# 01_Main.net
KiCad netlist of a schematic drawn in Altium Designer
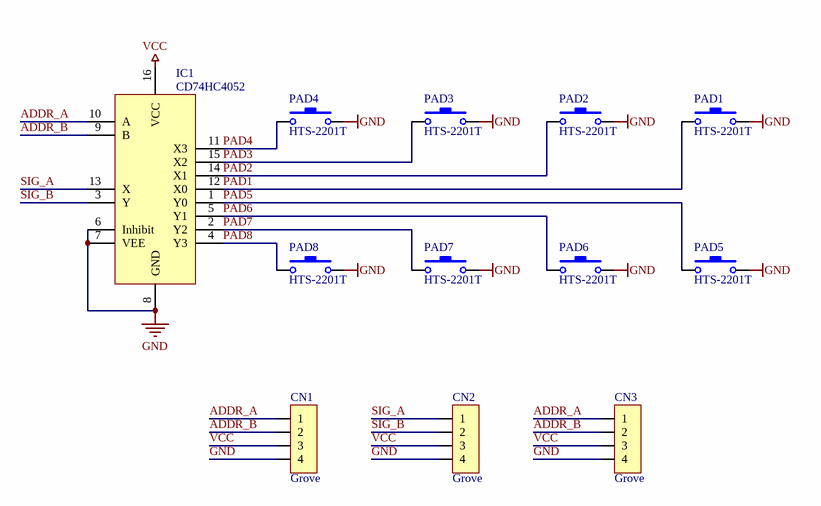
[diagram p0: 01.Main.SchDoc]

(export (version "E")
  (design (tool "Eeschema 10.0.6"))
  (components
    (comp (ref "CN1")
      (value "Grove")
      (footprint "Grove-4P-180D")
      (libsource (lib "MainnoLab library") (part "Connector 1X4"))
    )
    (comp (ref "CN2")
      (value "Grove")
      (footprint "Grove-4P-180D")
      (libsource (lib "MainnoLab library") (part "Connector 1X4"))
    )
    (comp (ref "CN3")
      (value "Grove")
      (footprint "Grove-4P-180D")
      (libsource (lib "MainnoLab library") (part "Connector 1X4"))
    )
    (comp (ref "IC1")
      (value "CD74HC4052")
      (footprint "SOIC16")
      (libsource (lib "MainnoLab library") (part "TC74HC4052AF"))
    )
    (comp (ref "PAD1")
      (value "HTS-2201T")
      (footprint "ALPS-SKHC-12mm")
      (libsource (lib "Jixuan's library") (part "Tact Switch HTS-2201T"))
    )
    (comp (ref "PAD2")
      (value "HTS-2201T")
      (footprint "ALPS-SKHC-12mm")
      (libsource (lib "Jixuan's library") (part "Tact Switch HTS-2201T"))
    )
    (comp (ref "PAD3")
      (value "HTS-2201T")
      (footprint "ALPS-SKHC-12mm")
      (libsource (lib "Jixuan's library") (part "Tact Switch HTS-2201T"))
    )
    (comp (ref "PAD4")
      (value "HTS-2201T")
      (footprint "ALPS-SKHC-12mm")
      (libsource (lib "Jixuan's library") (part "Tact Switch HTS-2201T"))
    )
    (comp (ref "PAD5")
      (value "HTS-2201T")
      (footprint "ALPS-SKHC-12mm")
      (libsource (lib "Jixuan's library") (part "Tact Switch HTS-2201T"))
    )
    (comp (ref "PAD6")
      (value "HTS-2201T")
      (footprint "ALPS-SKHC-12mm")
      (libsource (lib "Jixuan's library") (part "Tact Switch HTS-2201T"))
    )
    (comp (ref "PAD7")
      (value "HTS-2201T")
      (footprint "ALPS-SKHC-12mm")
      (libsource (lib "Jixuan's library") (part "Tact Switch HTS-2201T"))
    )
    (comp (ref "PAD8")
      (value "HTS-2201T")
      (footprint "ALPS-SKHC-12mm")
      (libsource (lib "Jixuan's library") (part "Tact Switch HTS-2201T"))
    )
  )
  (nets
    (net (code "1") (name "/ADDR_A") (class "Default")
      (node (ref "CN1") (pin "1") (pinfunction "1_1") (pintype "passive"))
      (node (ref "CN3") (pin "1") (pinfunction "1_1") (pintype "passive"))
      (node (ref "IC1") (pin "10") (pinfunction "A_10") (pintype "passive"))
    )
    (net (code "2") (name "/ADDR_B") (class "Default")
      (node (ref "CN1") (pin "2") (pinfunction "2_2") (pintype "passive"))
      (node (ref "CN3") (pin "2") (pinfunction "2_2") (pintype "passive"))
      (node (ref "IC1") (pin "9") (pinfunction "B_9") (pintype "passive"))
    )
    (net (code "3") (name "/PAD1") (class "Default")
      (node (ref "IC1") (pin "12") (pinfunction "X0_12") (pintype "passive"))
      (node (ref "PAD1") (pin "2") (pinfunction "2_2") (pintype "passive"))
    )
    (net (code "4") (name "/PAD2") (class "Default")
      (node (ref "IC1") (pin "14") (pinfunction "X1_14") (pintype "passive"))
      (node (ref "PAD2") (pin "2") (pinfunction "2_2") (pintype "passive"))
    )
    (net (code "5") (name "/PAD3") (class "Default")
      (node (ref "IC1") (pin "15") (pinfunction "X2_15") (pintype "passive"))
      (node (ref "PAD3") (pin "2") (pinfunction "2_2") (pintype "passive"))
    )
    (net (code "6") (name "/PAD4") (class "Default")
      (node (ref "IC1") (pin "11") (pinfunction "X3_11") (pintype "passive"))
      (node (ref "PAD4") (pin "2") (pinfunction "2_2") (pintype "passive"))
    )
    (net (code "7") (name "/PAD5") (class "Default")
      (node (ref "IC1") (pin "1") (pinfunction "Y0_1") (pintype "passive"))
      (node (ref "PAD5") (pin "2") (pinfunction "2_2") (pintype "passive"))
    )
    (net (code "8") (name "/PAD6") (class "Default")
      (node (ref "IC1") (pin "5") (pinfunction "Y1_5") (pintype "passive"))
      (node (ref "PAD6") (pin "2") (pinfunction "2_2") (pintype "passive"))
    )
    (net (code "9") (name "/PAD7") (class "Default")
      (node (ref "IC1") (pin "2") (pinfunction "Y2_2") (pintype "passive"))
      (node (ref "PAD7") (pin "2") (pinfunction "2_2") (pintype "passive"))
    )
    (net (code "10") (name "/PAD8") (class "Default")
      (node (ref "IC1") (pin "4") (pinfunction "Y3_4") (pintype "passive"))
      (node (ref "PAD8") (pin "2") (pinfunction "2_2") (pintype "passive"))
    )
    (net (code "11") (name "/SIG_A") (class "Default")
      (node (ref "CN2") (pin "1") (pinfunction "1_1") (pintype "passive"))
      (node (ref "IC1") (pin "13") (pinfunction "X_13") (pintype "passive"))
    )
    (net (code "12") (name "/SIG_B") (class "Default")
      (node (ref "CN2") (pin "2") (pinfunction "2_2") (pintype "passive"))
      (node (ref "IC1") (pin "3") (pinfunction "Y_3") (pintype "passive"))
    )
    (net (code "13") (name "GND") (class "Default")
      (node (ref "CN1") (pin "4") (pinfunction "4_4") (pintype "passive"))
      (node (ref "CN2") (pin "4") (pinfunction "4_4") (pintype "passive"))
      (node (ref "CN3") (pin "4") (pinfunction "4_4") (pintype "passive"))
      (node (ref "IC1") (pin "6") (pinfunction "Inhibit_6") (pintype "passive"))
      (node (ref "IC1") (pin "7") (pinfunction "VEE_7") (pintype "passive"))
      (node (ref "IC1") (pin "8") (pinfunction "GND_8") (pintype "passive"))
      (node (ref "PAD1") (pin "1") (pinfunction "1_1") (pintype "passive"))
      (node (ref "PAD2") (pin "1") (pinfunction "1_1") (pintype "passive"))
      (node (ref "PAD3") (pin "1") (pinfunction "1_1") (pintype "passive"))
      (node (ref "PAD4") (pin "1") (pinfunction "1_1") (pintype "passive"))
      (node (ref "PAD5") (pin "1") (pinfunction "1_1") (pintype "passive"))
      (node (ref "PAD6") (pin "1") (pinfunction "1_1") (pintype "passive"))
      (node (ref "PAD7") (pin "1") (pinfunction "1_1") (pintype "passive"))
      (node (ref "PAD8") (pin "1") (pinfunction "1_1") (pintype "passive"))
    )
    (net (code "14") (name "VCC") (class "Default")
      (node (ref "CN1") (pin "3") (pinfunction "3_3") (pintype "passive"))
      (node (ref "CN2") (pin "3") (pinfunction "3_3") (pintype "passive"))
      (node (ref "CN3") (pin "3") (pinfunction "3_3") (pintype "passive"))
      (node (ref "IC1") (pin "16") (pinfunction "VCC_16") (pintype "passive"))
    )
  )
)
